# FireFly.net
KiCad netlist of a schematic drawn in EAGLE
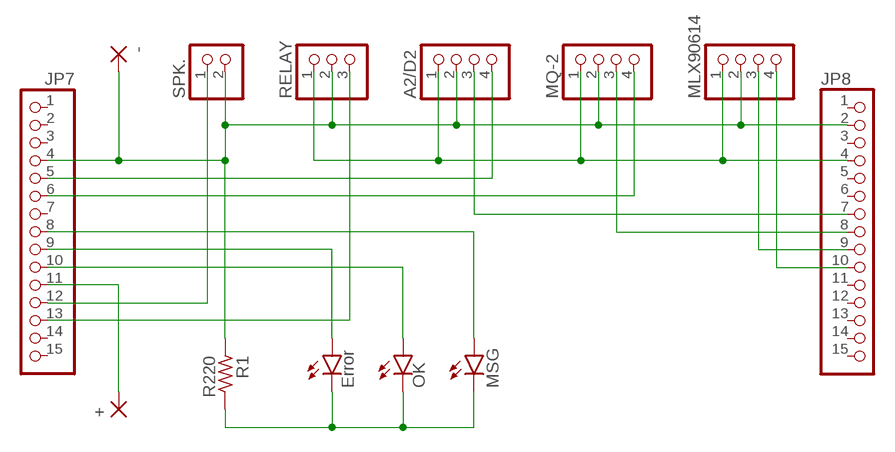
[diagram p0: schematic, sheet 1]

(export (version "E")
  (design (tool "Eeschema 10.0.6"))
  (components
    (comp (ref "+")
      (value "WIREPADSMD1,27-254")
      (footprint "eagle-import:SMD1,27-2,54")
      (libsource (lib "eagle-import") (part "WIREPADSMD1,27-254"))
    )
    (comp (ref "-")
      (value "WIREPADSMD1,27-254")
      (footprint "eagle-import:SMD1,27-2,54")
      (libsource (lib "eagle-import") (part "WIREPADSMD1,27-254"))
    )
    (comp (ref "A2/D2")
      (value "PINHD-1X4")
      (footprint "eagle-import:1X04")
      (libsource (lib "eagle-import") (part "PINHD-1X4"))
    )
    (comp (ref "JP7")
      (value "PINHD-1X15")
      (footprint "eagle-import:1X15")
      (libsource (lib "eagle-import") (part "PINHD-1X15"))
    )
    (comp (ref "JP8")
      (value "PINHD-1X15")
      (footprint "eagle-import:1X15")
      (libsource (lib "eagle-import") (part "PINHD-1X15"))
    )
    (comp (ref "LED2")
      (value "OK")
      (footprint "eagle-import:CHIPLED_0603")
      (libsource (lib "eagle-import") (part "LEDCHIPLED_0603"))
    )
    (comp (ref "LED3")
      (value "Error")
      (footprint "eagle-import:CHIPLED_0603")
      (libsource (lib "eagle-import") (part "LEDCHIPLED_0603"))
    )
    (comp (ref "MLX90614")
      (value "PINHD-1X4")
      (footprint "eagle-import:1X04")
      (libsource (lib "eagle-import") (part "PINHD-1X4"))
    )
    (comp (ref "MQ-2")
      (value "PINHD-1X4")
      (footprint "eagle-import:1X04")
      (libsource (lib "eagle-import") (part "PINHD-1X4"))
    )
    (comp (ref "MSG")
      (value "LEDCHIPLED_0603")
      (footprint "eagle-import:CHIPLED_0603")
      (libsource (lib "eagle-import") (part "LEDCHIPLED_0603"))
    )
    (comp (ref "R1")
      (value "R220")
      (footprint "eagle-import:R0603")
      (libsource (lib "eagle-import") (part "R_0603"))
    )
    (comp (ref "RELAY")
      (value "PINHD-1X3")
      (footprint "eagle-import:1X03")
      (libsource (lib "eagle-import") (part "PINHD-1X3"))
    )
    (comp (ref "SPK.")
      (value "PINHD-1X2")
      (footprint "eagle-import:1X02")
      (libsource (lib "eagle-import") (part "PINHD-1X2"))
    )
  )
  (nets
    (net (code "1") (name "Net-(+-P)") (class "Default")
      (node (ref "+") (pin "1") (pinfunction "P_1") (pintype "passive"))
      (node (ref "JP7") (pin "11") (pinfunction "11_11") (pintype "passive"))
    )
    (net (code "2") (name "Net-(--P)") (class "Default")
      (node (ref "-") (pin "1") (pinfunction "P_1") (pintype "passive"))
      (node (ref "A2/D2") (pin "2") (pinfunction "2_2") (pintype "passive"))
      (node (ref "JP7") (pin "4") (pinfunction "4_4") (pintype "passive"))
      (node (ref "JP8") (pin "2") (pinfunction "2_2") (pintype "passive"))
      (node (ref "MLX90614") (pin "2") (pinfunction "2_2") (pintype "passive"))
      (node (ref "MQ-2") (pin "2") (pinfunction "2_2") (pintype "passive"))
      (node (ref "R1") (pin "1") (pinfunction "1_1") (pintype "passive"))
      (node (ref "RELAY") (pin "2") (pinfunction "2_2") (pintype "passive"))
      (node (ref "SPK.") (pin "2") (pinfunction "2_2") (pintype "passive"))
    )
    (net (code "3") (name "Net-(A2/D2-Pad1)") (class "Default")
      (node (ref "A2/D2") (pin "1") (pinfunction "1_1") (pintype "passive"))
      (node (ref "JP8") (pin "4") (pinfunction "4_4") (pintype "passive"))
      (node (ref "MLX90614") (pin "1") (pinfunction "1_1") (pintype "passive"))
      (node (ref "MQ-2") (pin "1") (pinfunction "1_1") (pintype "passive"))
      (node (ref "RELAY") (pin "1") (pinfunction "1_1") (pintype "passive"))
    )
    (net (code "4") (name "Net-(A2/D2-Pad3)") (class "Default")
      (node (ref "A2/D2") (pin "3") (pinfunction "3_3") (pintype "passive"))
      (node (ref "JP8") (pin "7") (pinfunction "7_7") (pintype "passive"))
    )
    (net (code "5") (name "Net-(A2/D2-Pad4)") (class "Default")
      (node (ref "A2/D2") (pin "4") (pinfunction "4_4") (pintype "passive"))
      (node (ref "JP7") (pin "5") (pinfunction "5_5") (pintype "passive"))
    )
    (net (code "6") (name "Net-(JP7-Pad6)") (class "Default")
      (node (ref "JP7") (pin "6") (pinfunction "6_6") (pintype "passive"))
      (node (ref "MQ-2") (pin "4") (pinfunction "4_4") (pintype "passive"))
    )
    (net (code "7") (name "Net-(JP7-Pad8)") (class "Default")
      (node (ref "JP7") (pin "8") (pinfunction "8_8") (pintype "passive"))
      (node (ref "MSG") (pin "A") (pinfunction "A_A") (pintype "passive"))
    )
    (net (code "8") (name "Net-(JP7-Pad9)") (class "Default")
      (node (ref "JP7") (pin "9") (pinfunction "9_9") (pintype "passive"))
      (node (ref "LED3") (pin "A") (pinfunction "A_A") (pintype "passive"))
    )
    (net (code "9") (name "Net-(JP7-Pad10)") (class "Default")
      (node (ref "JP7") (pin "10") (pinfunction "10_10") (pintype "passive"))
      (node (ref "LED2") (pin "A") (pinfunction "A_A") (pintype "passive"))
    )
    (net (code "10") (name "Net-(JP7-Pad12)") (class "Default")
      (node (ref "JP7") (pin "12") (pinfunction "12_12") (pintype "passive"))
      (node (ref "SPK.") (pin "1") (pinfunction "1_1") (pintype "passive"))
    )
    (net (code "11") (name "Net-(JP7-Pad13)") (class "Default")
      (node (ref "JP7") (pin "13") (pinfunction "13_13") (pintype "passive"))
      (node (ref "RELAY") (pin "3") (pinfunction "3_3") (pintype "passive"))
    )
    (net (code "12") (name "Net-(JP8-Pad8)") (class "Default")
      (node (ref "JP8") (pin "8") (pinfunction "8_8") (pintype "passive"))
      (node (ref "MQ-2") (pin "3") (pinfunction "3_3") (pintype "passive"))
    )
    (net (code "13") (name "Net-(JP8-Pad9)") (class "Default")
      (node (ref "JP8") (pin "9") (pinfunction "9_9") (pintype "passive"))
      (node (ref "MLX90614") (pin "3") (pinfunction "3_3") (pintype "passive"))
    )
    (net (code "14") (name "Net-(JP8-Pad10)") (class "Default")
      (node (ref "JP8") (pin "10") (pinfunction "10_10") (pintype "passive"))
      (node (ref "MLX90614") (pin "4") (pinfunction "4_4") (pintype "passive"))
    )
    (net (code "15") (name "Net-(LED2-PadC)") (class "Default")
      (node (ref "LED2") (pin "C") (pinfunction "C_C") (pintype "passive"))
      (node (ref "LED3") (pin "C") (pinfunction "C_C") (pintype "passive"))
      (node (ref "MSG") (pin "C") (pinfunction "C_C") (pintype "passive"))
      (node (ref "R1") (pin "2") (pinfunction "2_2") (pintype "passive"))
    )
    (net (code "16") (name "unconnected-(JP7-Pad1)") (class "Default")
      (node (ref "JP7") (pin "1") (pinfunction "1_1") (pintype "passive"))
    )
    (net (code "17") (name "unconnected-(JP7-Pad2)") (class "Default")
      (node (ref "JP7") (pin "2") (pinfunction "2_2") (pintype "passive"))
    )
    (net (code "18") (name "unconnected-(JP7-Pad3)") (class "Default")
      (node (ref "JP7") (pin "3") (pinfunction "3_3") (pintype "passive"))
    )
    (net (code "19") (name "unconnected-(JP7-Pad7)") (class "Default")
      (node (ref "JP7") (pin "7") (pinfunction "7_7") (pintype "passive"))
    )
    (net (code "20") (name "unconnected-(JP7-Pad14)") (class "Default")
      (node (ref "JP7") (pin "14") (pinfunction "14_14") (pintype "passive"))
    )
    (net (code "21") (name "unconnected-(JP7-Pad15)") (class "Default")
      (node (ref "JP7") (pin "15") (pinfunction "15_15") (pintype "passive"))
    )
    (net (code "22") (name "unconnected-(JP8-Pad1)") (class "Default")
      (node (ref "JP8") (pin "1") (pinfunction "1_1") (pintype "passive"))
    )
    (net (code "23") (name "unconnected-(JP8-Pad3)") (class "Default")
      (node (ref "JP8") (pin "3") (pinfunction "3_3") (pintype "passive"))
    )
    (net (code "24") (name "unconnected-(JP8-Pad5)") (class "Default")
      (node (ref "JP8") (pin "5") (pinfunction "5_5") (pintype "passive"))
    )
    (net (code "25") (name "unconnected-(JP8-Pad6)") (class "Default")
      (node (ref "JP8") (pin "6") (pinfunction "6_6") (pintype "passive"))
    )
    (net (code "26") (name "unconnected-(JP8-Pad11)") (class "Default")
      (node (ref "JP8") (pin "11") (pinfunction "11_11") (pintype "passive"))
    )
    (net (code "27") (name "unconnected-(JP8-Pad12)") (class "Default")
      (node (ref "JP8") (pin "12") (pinfunction "12_12") (pintype "passive"))
    )
    (net (code "28") (name "unconnected-(JP8-Pad13)") (class "Default")
      (node (ref "JP8") (pin "13") (pinfunction "13_13") (pintype "passive"))
    )
    (net (code "29") (name "unconnected-(JP8-Pad14)") (class "Default")
      (node (ref "JP8") (pin "14") (pinfunction "14_14") (pintype "passive"))
    )
    (net (code "30") (name "unconnected-(JP8-Pad15)") (class "Default")
      (node (ref "JP8") (pin "15") (pinfunction "15_15") (pintype "passive"))
    )
  )
)
